# 1_Sheet_1_schdoc.net
KiCad netlist of a schematic drawn in Altium Designer
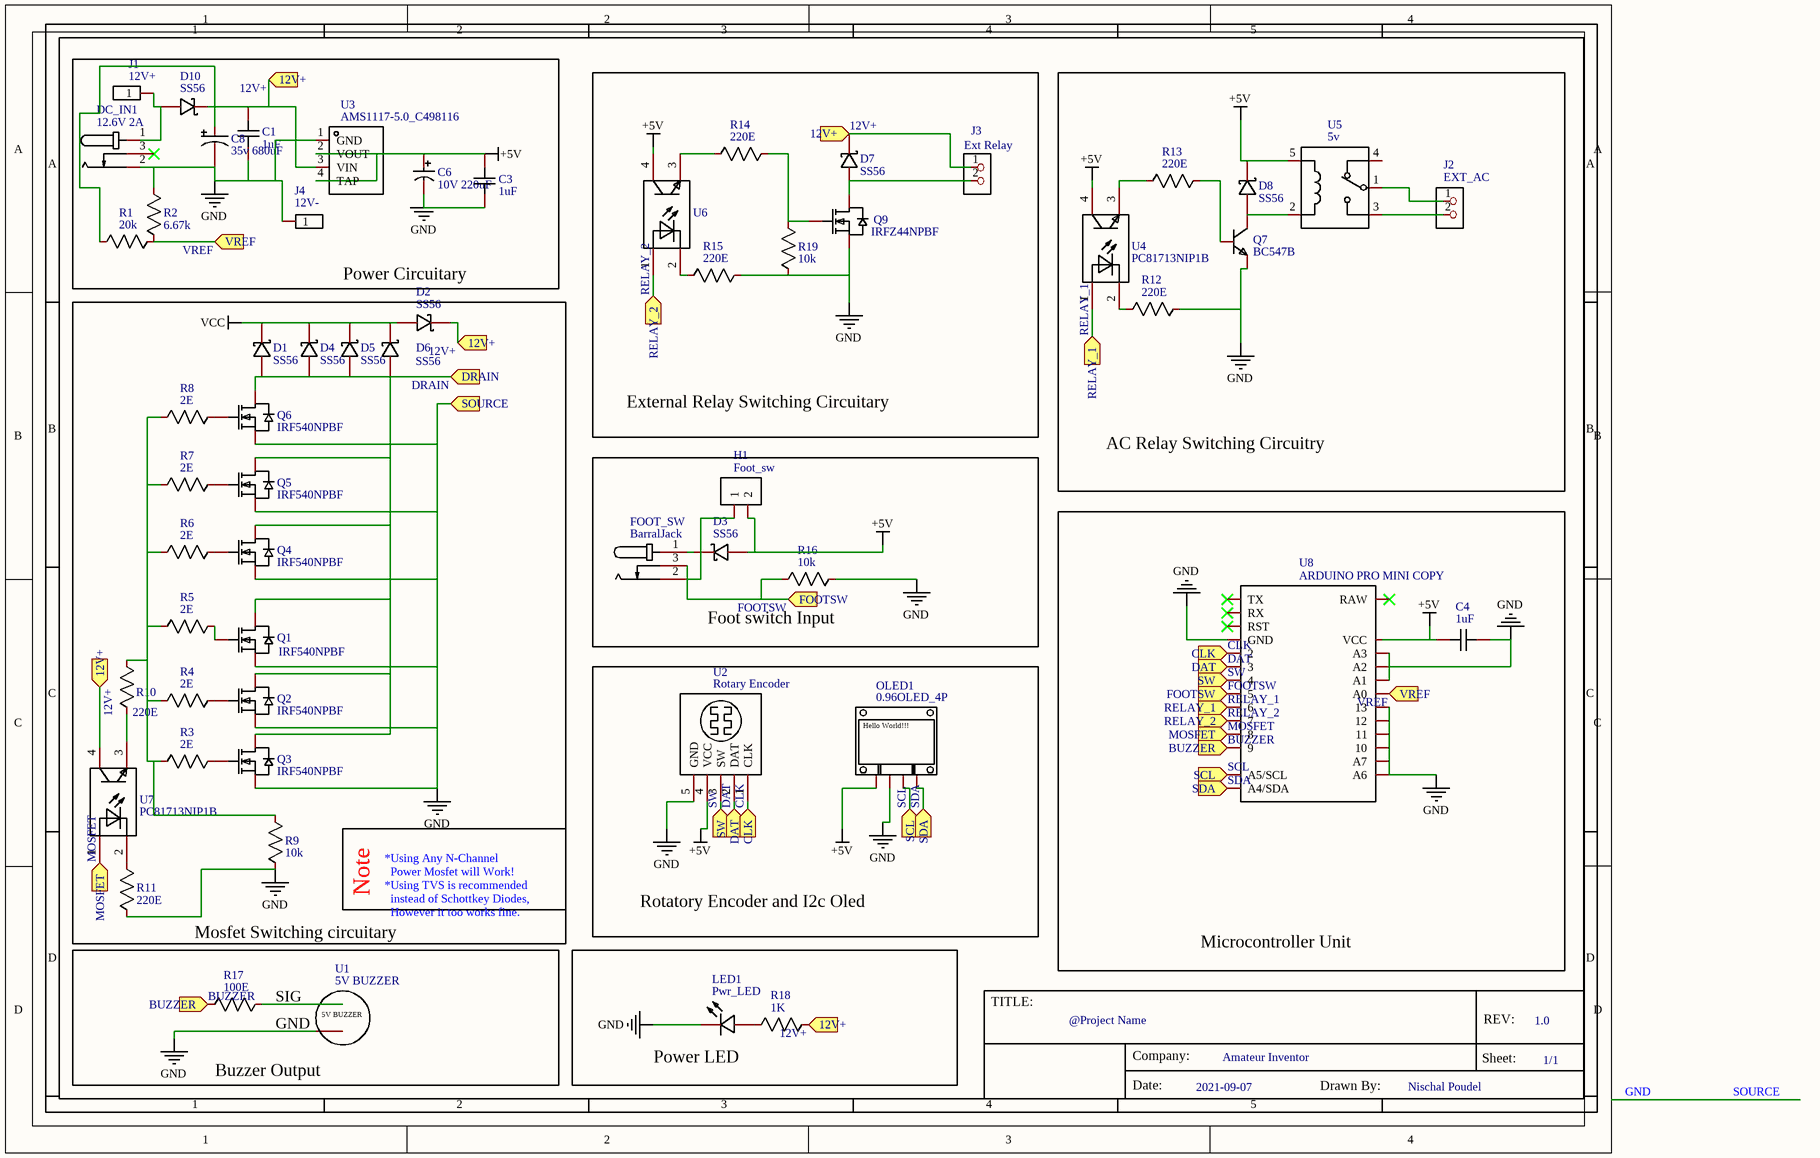
[diagram p0: 1_Sheet_1.schdoc.schdoc]

(export (version "E")
  (design (tool "Eeschema 10.0.6"))
  (components
    (comp (ref "C1")
      (value "1uF")
      (fields
        (field (name "NAME") "1uF")
        (field (name "MANUFACTURER") "FH")
        (field (name "MANUFACTURER PART") "0603B105K160NT")
      )
      (libsource (lib "altium-import") (part "root_1_0603B105K160NT_"))
    )
    (comp (ref "C3")
      (value "1uF")
      (fields
        (field (name "NAME") "1uF")
        (field (name "MANUFACTURER") "FH")
        (field (name "MANUFACTURER PART") "0603B105K160NT")
      )
      (libsource (lib "altium-import") (part "root_1_0603B105K160NT_"))
    )
    (comp (ref "C4")
      (value "1uF")
      (fields
        (field (name "NAME") "1uF")
        (field (name "MANUFACTURER") "FH")
        (field (name "MANUFACTURER PART") "0603B105K160NT")
      )
      (libsource (lib "altium-import") (part "root_2_0603B105K160NT_"))
    )
    (comp (ref "C6")
      (value "10V 220uF")
      (fields
        (field (name "NAME") "10V 220uF")
        (field (name "MANUFACTURER") "ValuePro")
        (field (name "MANUFACTURER PART") "220uF 10V black gold 5*11")
      )
      (libsource (lib "altium-import") (part "root_3_220uF 10V black gold 5*11_"))
    )
    (comp (ref "C8")
      (value "35v 680uF")
      (fields
        (field (name "NAME") "35v 680uF")
        (field (name "MANUFACTURER") "BERYL Electronic Tech")
        (field (name "MANUFACTURER PART") "RC035M681LO10*16TH-2A1E")
      )
      (libsource (lib "altium-import") (part "root_3_RC035M681LO10*16TH-2A1E_"))
    )
    (comp (ref "D1")
      (value "SS56")
      (fields (field (name "NAME") "SS56") (field (name "MANUFACTURER") "High Diode"))
      (libsource (lib "altium-import") (part "root_3_SS56_"))
    )
    (comp (ref "D2")
      (value "SS56")
      (fields (field (name "NAME") "SS56") (field (name "MANUFACTURER") "High Diode"))
      (libsource (lib "altium-import") (part "root_2_SS56_"))
    )
    (comp (ref "D3")
      (value "SS56")
      (fields (field (name "NAME") "SS56") (field (name "MANUFACTURER") "High Diode"))
      (libsource (lib "altium-import") (part "root_0_SS56_"))
    )
    (comp (ref "D4")
      (value "SS56")
      (fields (field (name "NAME") "SS56") (field (name "MANUFACTURER") "High Diode"))
      (libsource (lib "altium-import") (part "root_3_SS56_"))
    )
    (comp (ref "D5")
      (value "SS56")
      (fields (field (name "NAME") "SS56") (field (name "MANUFACTURER") "High Diode"))
      (libsource (lib "altium-import") (part "root_3_SS56_"))
    )
    (comp (ref "D6")
      (value "SS56")
      (fields (field (name "NAME") "SS56") (field (name "MANUFACTURER") "High Diode"))
      (libsource (lib "altium-import") (part "root_3_SS56_"))
    )
    (comp (ref "D7")
      (value "SS56")
      (fields (field (name "NAME") "SS56") (field (name "MANUFACTURER") "High Diode"))
      (libsource (lib "altium-import") (part "root_3_SS56_"))
    )
    (comp (ref "D8")
      (value "SS56")
      (fields (field (name "NAME") "SS56") (field (name "MANUFACTURER") "High Diode"))
      (libsource (lib "altium-import") (part "root_3_SS56_"))
    )
    (comp (ref "D10")
      (value "SS56")
      (fields (field (name "NAME") "SS56") (field (name "MANUFACTURER") "High Diode"))
      (libsource (lib "altium-import") (part "root_2_SS56_"))
    )
    (comp (ref "DC_IN1")
      (value "12.6V 2A")
      (fields
        (field (name "NAME") "12.6V 2A")
        (field (name "MANUFACTURER") "XKB Enterprise")
        (field (name "MANUFACTURER PART") "DC-005B-2.5A-2.0")
      )
      (libsource (lib "altium-import") (part "root_0_DC-005B-2.5A-2.0_"))
    )
    (comp (ref "FOOT_SW")
      (value "BarralJack")
      (fields
        (field (name "NAME") "BarralJack")
        (field (name "MANUFACTURER") "XKB Enterprise")
        (field (name "MANUFACTURER PART") "DC-005B-2.5A-2.0")
      )
      (libsource (lib "altium-import") (part "root_0_DC-005B-2.5A-2.0_"))
    )
    (comp (ref "H1")
      (value "Foot_sw")
      (fields (field (name "NAME") "Foot_sw"))
      (libsource (lib "altium-import") (part "root_1_Foot_sw_"))
    )
    (comp (ref "J1")
      (value "12V+")
      (fields (field (name "NAME") "12V+"))
      (libsource (lib "altium-import") (part "root_2_12V+_"))
    )
    (comp (ref "J2")
      (value "EXT_AC")
      (fields (field (name "NAME") "EXT_AC"))
      (libsource (lib "altium-import") (part "root_0_EXT_AC_"))
    )
    (comp (ref "J3")
      (value "Ext Relay")
      (fields (field (name "NAME") "Ext Relay"))
      (libsource (lib "altium-import") (part "root_0_Ext Relay_"))
    )
    (comp (ref "J4")
      (value "12V-")
      (fields (field (name "NAME") "12V-"))
      (libsource (lib "altium-import") (part "root_0_12V-_"))
    )
    (comp (ref "LED1")
      (value "Pwr_LED")
      (fields
        (field (name "NAME") "Pwr_LED")
        (field (name "MANUFACTURER") "TOGIALED")
        (field (name "MANUFACTURER PART") "TJ-S1608SW6TGLC2G-A5")
      )
      (libsource (lib "altium-import") (part "root_0_TJ-S1608SW6TGLC2G-A5_"))
    )
    (comp (ref "OLED1")
      (value "0.96OLED_4P")
      (fields (field (name "NAME") "0.96OLED_4P"))
      (libsource (lib "altium-import") (part "root_0_0.96OLED_4P_"))
    )
    (comp (ref "Q1")
      (value "IRF540NPBF")
      (fields (field (name "NAME") "IRF540NPBF") (field (name "MANUFACTURER") "Infineon"))
      (libsource (lib "altium-import") (part "root_0_IRF540NPBF_"))
    )
    (comp (ref "Q2")
      (value "IRF540NPBF")
      (fields (field (name "NAME") "IRF540NPBF") (field (name "MANUFACTURER") "Infineon"))
      (libsource (lib "altium-import") (part "root_0_IRF540NPBF_"))
    )
    (comp (ref "Q3")
      (value "IRF540NPBF")
      (fields (field (name "NAME") "IRF540NPBF") (field (name "MANUFACTURER") "Infineon"))
      (libsource (lib "altium-import") (part "root_0_IRF540NPBF_"))
    )
    (comp (ref "Q4")
      (value "IRF540NPBF")
      (fields (field (name "NAME") "IRF540NPBF") (field (name "MANUFACTURER") "Infineon"))
      (libsource (lib "altium-import") (part "root_0_IRF540NPBF_"))
    )
    (comp (ref "Q5")
      (value "IRF540NPBF")
      (fields (field (name "NAME") "IRF540NPBF") (field (name "MANUFACTURER") "Infineon"))
      (libsource (lib "altium-import") (part "root_0_IRF540NPBF_"))
    )
    (comp (ref "Q6")
      (value "IRF540NPBF")
      (fields (field (name "NAME") "IRF540NPBF") (field (name "MANUFACTURER") "Infineon"))
      (libsource (lib "altium-import") (part "root_0_IRF540NPBF_"))
    )
    (comp (ref "Q7")
      (value "BC547B")
      (fields (field (name "NAME") "BC547B") (field (name "MANUFACTURER") "LGE"))
      (libsource (lib "altium-import") (part "root_0_BC547B_"))
    )
    (comp (ref "Q9")
      (value "IRFZ44NPBF")
      (fields (field (name "NAME") "IRFZ44NPBF") (field (name "MANUFACTURER") "Infineon(英飞凌)"))
      (libsource (lib "altium-import") (part "root_0_IRFZ44NPBF_"))
    )
    (comp (ref "R1")
      (value "20k")
      (fields (field (name "NAME") "20k"))
      (libsource (lib "altium-import") (part "root_0_20k_"))
    )
    (comp (ref "R2")
      (value "6.67k")
      (fields (field (name "NAME") "6.67k"))
      (libsource (lib "altium-import") (part "root_3_6.67k_"))
    )
    (comp (ref "R3")
      (value "2E")
      (fields (field (name "NAME") "2E"))
      (libsource (lib "altium-import") (part "root_0_2E_"))
    )
    (comp (ref "R4")
      (value "2E")
      (fields (field (name "NAME") "2E"))
      (libsource (lib "altium-import") (part "root_0_2E_"))
    )
    (comp (ref "R5")
      (value "2E")
      (fields (field (name "NAME") "2E"))
      (libsource (lib "altium-import") (part "root_0_2E_"))
    )
    (comp (ref "R6")
      (value "2E")
      (fields (field (name "NAME") "2E"))
      (libsource (lib "altium-import") (part "root_0_2E_"))
    )
    (comp (ref "R7")
      (value "2E")
      (fields (field (name "NAME") "2E"))
      (libsource (lib "altium-import") (part "root_0_2E_"))
    )
    (comp (ref "R8")
      (value "2E")
      (fields (field (name "NAME") "2E"))
      (libsource (lib "altium-import") (part "root_0_2E_"))
    )
    (comp (ref "R9")
      (value "10k")
      (fields (field (name "NAME") "10k"))
      (libsource (lib "altium-import") (part "root_1_10k_"))
    )
    (comp (ref "R10")
      (value "220E")
      (fields (field (name "NAME") "220E"))
      (libsource (lib "altium-import") (part "root_1_220E_"))
    )
    (comp (ref "R11")
      (value "220E")
      (fields (field (name "NAME") "220E"))
      (libsource (lib "altium-import") (part "root_1_220E_"))
    )
    (comp (ref "R12")
      (value "220E")
      (fields (field (name "NAME") "220E"))
      (libsource (lib "altium-import") (part "root_2_220E_"))
    )
    (comp (ref "R13")
      (value "220E")
      (fields (field (name "NAME") "220E"))
      (libsource (lib "altium-import") (part "root_0_220E_"))
    )
    (comp (ref "R14")
      (value "220E")
      (fields (field (name "NAME") "220E"))
      (libsource (lib "altium-import") (part "root_0_220E_"))
    )
    (comp (ref "R15")
      (value "220E")
      (fields (field (name "NAME") "220E"))
      (libsource (lib "altium-import") (part "root_2_220E_"))
    )
    (comp (ref "R16")
      (value "10k")
      (fields (field (name "NAME") "10k"))
      (libsource (lib "altium-import") (part "root_2_10k_"))
    )
    (comp (ref "R17")
      (value "100E")
      (fields (field (name "NAME") "100E"))
      (libsource (lib "altium-import") (part "root_2_100E_"))
    )
    (comp (ref "R18")
      (value "1K")
      (fields (field (name "NAME") "1K"))
      (libsource (lib "altium-import") (part "root_2_1K_"))
    )
    (comp (ref "R19")
      (value "10k")
      (fields (field (name "NAME") "10k"))
      (libsource (lib "altium-import") (part "root_3_10k_"))
    )
    (comp (ref "U1")
      (value "5V BUZZER")
      (fields (field (name "NAME") "5V BUZZER"))
      (libsource (lib "altium-import") (part "root_0_5V BUZZER_"))
    )
    (comp (ref "U2")
      (value "Rotary Encoder")
      (fields (field (name "NAME") "Rotary Encoder") (field (name "MANUFACTURER PART") "encoder"))
      (libsource (lib "altium-import") (part "root_3_encoder_"))
    )
    (comp (ref "U3")
      (value "AMS1117-5.0_C498116")
      (fields
        (field (name "NAME") "AMS1117-5.0_C498116")
        (field (name "MANUFACTURER") "HGC(Huaguan Semicon)")
        (field (name "MANUFACTURER PART") "AMS1117-5.0")
      )
      (libsource (lib "altium-import") (part "root_0_AMS1117-5.0_"))
    )
    (comp (ref "U4")
      (value "PC81713NIP1B")
      (fields (field (name "NAME") "PC81713NIP1B") (field (name "MANUFACTURER") "Sharp Microelectronics"))
      (libsource (lib "altium-import") (part "root_1_PC81713NIP1B_"))
    )
    (comp (ref "U5")
      (value "5v")
      (fields (field (name "NAME") "5v"))
      (libsource (lib "altium-import") (part "root_0_5v_"))
    )
    (comp (ref "U6")
      (value "PC81713NIP1B")
      (fields (field (name "MANUFACTURER") "Sharp Microelectronics"))
      (libsource (lib "altium-import") (part "root_1_PC81713NIP1B_"))
    )
    (comp (ref "U7")
      (value "PC81713NIP1B")
      (fields (field (name "NAME") "PC81713NIP1B") (field (name "MANUFACTURER") "Sharp Microelectronics"))
      (libsource (lib "altium-import") (part "root_1_PC81713NIP1B_"))
    )
    (comp (ref "U8")
      (value "ARDUINO PRO MINI COPY")
      (description "Arduino Pro Mini footprint")
      (fields (field (name "NAME") "ARDUINO PRO MINI COPY"))
      (libsource (lib "altium-import") (part "root_0_ARDUINO PRO MINI COPY_"))
    )
  )
  (nets
    (net (code "1") (name "+5V") (class "Default")
      (node (ref "C3") (pin "2") (pinfunction "2_2") (pintype "passive"))
      (node (ref "C4") (pin "2") (pinfunction "2_2") (pintype "passive"))
      (node (ref "C6") (pin "1") (pinfunction "1_1") (pintype "passive"))
      (node (ref "D3") (pin "2") (pinfunction "2_2") (pintype "passive"))
      (node (ref "D8") (pin "1") (pinfunction "1_1") (pintype "passive"))
      (node (ref "H1") (pin "2") (pinfunction "2_2") (pintype "passive"))
      (node (ref "OLED1") (pin "1") (pinfunction "1_1") (pintype "passive"))
      (node (ref "U2") (pin "4") (pinfunction "VCC_4") (pintype "passive"))
      (node (ref "U3") (pin "2") (pinfunction "VOUT_2") (pintype "passive"))
      (node (ref "U3") (pin "4") (pinfunction "TAP_4") (pintype "passive"))
      (node (ref "U4") (pin "4") (pinfunction "Collector_4") (pintype "passive"))
      (node (ref "U5") (pin "5") (pinfunction "5_5") (pintype "passive"))
      (node (ref "U6") (pin "4") (pinfunction "Collector_4") (pintype "passive"))
      (node (ref "U8") (pin "VCC") (pinfunction "VCC_VCC") (pintype "passive"))
    )
    (net (code "2") (name "/12V+") (class "Default")
      (node (ref "C1") (pin "2") (pinfunction "2_2") (pintype "passive"))
      (node (ref "C8") (pin "1") (pinfunction "1_1") (pintype "passive"))
      (node (ref "D10") (pin "1") (pinfunction "1_1") (pintype "passive"))
      (node (ref "D2") (pin "1") (pinfunction "1_1") (pintype "passive"))
      (node (ref "D7") (pin "1") (pinfunction "1_1") (pintype "passive"))
      (node (ref "J3") (pin "1") (pinfunction "1_1") (pintype "passive"))
      (node (ref "R1") (pin "1") (pinfunction "1_1") (pintype "passive"))
      (node (ref "R18") (pin "1") (pinfunction "1_1") (pintype "passive"))
      (node (ref "U3") (pin "3") (pinfunction "VIN_3") (pintype "passive"))
      (node (ref "U7") (pin "4") (pinfunction "Collector_4") (pintype "passive"))
    )
    (net (code "3") (name "/BUZZER") (class "Default")
      (node (ref "R17") (pin "2") (pinfunction "2_2") (pintype "passive"))
      (node (ref "U8") (pin "D9") (pinfunction "9_D9") (pintype "passive"))
    )
    (net (code "4") (name "/CLK") (class "Default")
      (node (ref "U2") (pin "1") (pinfunction "CLK_1") (pintype "passive"))
      (node (ref "U8") (pin "D2") (pinfunction "2_D2") (pintype "passive"))
    )
    (net (code "5") (name "/DAT") (class "Default")
      (node (ref "U2") (pin "2") (pinfunction "DAT_2") (pintype "passive"))
      (node (ref "U8") (pin "D3") (pinfunction "3_D3") (pintype "passive"))
    )
    (net (code "6") (name "/DRAIN") (class "Default")
      (node (ref "D1") (pin "2") (pinfunction "2_2") (pintype "passive"))
      (node (ref "D4") (pin "2") (pinfunction "2_2") (pintype "passive"))
      (node (ref "D5") (pin "2") (pinfunction "2_2") (pintype "passive"))
      (node (ref "D6") (pin "2") (pinfunction "2_2") (pintype "passive"))
      (node (ref "Q1") (pin "2") (pinfunction "D_2") (pintype "passive"))
      (node (ref "Q2") (pin "2") (pinfunction "D_2") (pintype "passive"))
      (node (ref "Q3") (pin "2") (pinfunction "D_2") (pintype "passive"))
      (node (ref "Q4") (pin "2") (pinfunction "D_2") (pintype "passive"))
      (node (ref "Q5") (pin "2") (pinfunction "D_2") (pintype "passive"))
      (node (ref "Q6") (pin "2") (pinfunction "D_2") (pintype "passive"))
    )
    (net (code "7") (name "/FOOTSW") (class "Default")
      (node (ref "FOOT_SW") (pin "2") (pinfunction "2_2") (pintype "passive"))
      (node (ref "FOOT_SW") (pin "3") (pinfunction "3_3") (pintype "passive"))
      (node (ref "H1") (pin "1") (pinfunction "1_1") (pintype "passive"))
      (node (ref "R16") (pin "2") (pinfunction "2_2") (pintype "passive"))
      (node (ref "U8") (pin "D5") (pinfunction "5_D5") (pintype "passive"))
    )
    (net (code "8") (name "/MOSFET") (class "Default")
      (node (ref "U7") (pin "1") (pinfunction "Anode_1") (pintype "passive"))
      (node (ref "U8") (pin "D8") (pinfunction "8_D8") (pintype "passive"))
    )
    (net (code "9") (name "/RELAY_1") (class "Default")
      (node (ref "U4") (pin "1") (pinfunction "Anode_1") (pintype "passive"))
      (node (ref "U8") (pin "D6") (pinfunction "6_D6") (pintype "passive"))
    )
    (net (code "10") (name "/RELAY_2") (class "Default")
      (node (ref "U6") (pin "1") (pinfunction "Anode_1") (pintype "passive"))
      (node (ref "U8") (pin "D7") (pinfunction "7_D7") (pintype "passive"))
    )
    (net (code "11") (name "/SCL") (class "Default")
      (node (ref "OLED1") (pin "3") (pinfunction "3_3") (pintype "passive"))
      (node (ref "U8") (pin "A5") (pinfunction "A5/SCL_A5") (pintype "passive"))
    )
    (net (code "12") (name "/SDA") (class "Default")
      (node (ref "OLED1") (pin "4") (pinfunction "4_4") (pintype "passive"))
      (node (ref "U8") (pin "A4") (pinfunction "A4/SDA_A4") (pintype "passive"))
    )
    (net (code "13") (name "/SW") (class "Default")
      (node (ref "U2") (pin "3") (pinfunction "SW_3") (pintype "passive"))
      (node (ref "U8") (pin "D4") (pinfunction "4_D4") (pintype "passive"))
    )
    (net (code "14") (name "/VREF") (class "Default")
      (node (ref "R1") (pin "2") (pinfunction "2_2") (pintype "passive"))
      (node (ref "R2") (pin "2") (pinfunction "2_2") (pintype "passive"))
      (node (ref "U8") (pin "A0") (pinfunction "A0_A0") (pintype "passive"))
    )
    (net (code "15") (name "GND") (class "Default")
      (node (ref "C1") (pin "1") (pinfunction "1_1") (pintype "passive"))
      (node (ref "C3") (pin "1") (pinfunction "1_1") (pintype "passive"))
      (node (ref "C4") (pin "1") (pinfunction "1_1") (pintype "passive"))
      (node (ref "C6") (pin "2") (pinfunction "2_2") (pintype "passive"))
      (node (ref "C8") (pin "2") (pinfunction "2_2") (pintype "passive"))
      (node (ref "DC_IN1") (pin "2") (pinfunction "2_2") (pintype "passive"))
      (node (ref "J4") (pin "1") (pinfunction "1_1") (pintype "passive"))
      (node (ref "LED1") (pin "1") (pinfunction "-_1") (pintype "passive"))
      (node (ref "OLED1") (pin "2") (pinfunction "2_2") (pintype "passive"))
      (node (ref "Q1") (pin "3") (pinfunction "S_3") (pintype "passive"))
      (node (ref "Q2") (pin "3") (pinfunction "S_3") (pintype "passive"))
      (node (ref "Q3") (pin "3") (pinfunction "S_3") (pintype "passive"))
      (node (ref "Q4") (pin "3") (pinfunction "S_3") (pintype "passive"))
      (node (ref "Q5") (pin "3") (pinfunction "S_3") (pintype "passive"))
      (node (ref "Q6") (pin "3") (pinfunction "S_3") (pintype "passive"))
      (node (ref "Q7") (pin "3") (pinfunction "E_3") (pintype "passive"))
      (node (ref "Q9") (pin "3") (pinfunction "S_3") (pintype "passive"))
      (node (ref "R11") (pin "1") (pinfunction "1_1") (pintype "passive"))
      (node (ref "R12") (pin "1") (pinfunction "1_1") (pintype "passive"))
      (node (ref "R15") (pin "1") (pinfunction "1_1") (pintype "passive"))
      (node (ref "R16") (pin "1") (pinfunction "1_1") (pintype "passive"))
      (node (ref "R19") (pin "2") (pinfunction "2_2") (pintype "passive"))
      (node (ref "R2") (pin "1") (pinfunction "1_1") (pintype "passive"))
      (node (ref "R9") (pin "1") (pinfunction "1_1") (pintype "passive"))
      (node (ref "U2") (pin "5") (pinfunction "GND_5") (pintype "passive"))
      (node (ref "U3") (pin "1") (pinfunction "GND_1") (pintype "passive"))
      (node (ref "U8") (pin "A1") (pinfunction "A1_A1") (pintype "passive"))
      (node (ref "U8") (pin "A2") (pinfunction "A2_A2") (pintype "passive"))
      (node (ref "U8") (pin "A3") (pinfunction "A3_A3") (pintype "passive"))
      (node (ref "U8") (pin "A6") (pinfunction "A6_A6") (pintype "passive"))
      (node (ref "U8") (pin "A7") (pinfunction "A7_A7") (pintype "passive"))
      (node (ref "U8") (pin "D10") (pinfunction "10_D10") (pintype "passive"))
      (node (ref "U8") (pin "D11") (pinfunction "11_D11") (pintype "passive"))
      (node (ref "U8") (pin "D12") (pinfunction "12_D12") (pintype "passive"))
      (node (ref "U8") (pin "D13") (pinfunction "13_D13") (pintype "passive"))
      (node (ref "U8") (pin "GND") (pinfunction "GND_GND") (pintype "passive"))
    )
    (net (code "16") (name "Net-(D3-Pad1)") (class "Default")
      (node (ref "D3") (pin "1") (pinfunction "1_1") (pintype "passive"))
      (node (ref "FOOT_SW") (pin "1") (pinfunction "1_1") (pintype "passive"))
    )
    (net (code "17") (name "Net-(D10-Pad2)") (class "Default")
      (node (ref "D10") (pin "2") (pinfunction "2_2") (pintype "passive"))
      (node (ref "DC_IN1") (pin "1") (pinfunction "1_1") (pintype "passive"))
      (node (ref "J1") (pin "1") (pinfunction "1_1") (pintype "passive"))
    )
    (net (code "18") (name "Net-(J2-Pad1)") (class "Default")
      (node (ref "J2") (pin "1") (pinfunction "1_1") (pintype "passive"))
      (node (ref "U5") (pin "1") (pinfunction "1_1") (pintype "passive"))
    )
    (net (code "19") (name "Net-(J2-Pad2)") (class "Default")
      (node (ref "J2") (pin "2") (pinfunction "2_2") (pintype "passive"))
      (node (ref "U5") (pin "3") (pinfunction "3_3") (pintype "passive"))
    )
    (net (code "20") (name "Net-(LED1-+)") (class "Default")
      (node (ref "LED1") (pin "2") (pinfunction "+_2") (pintype "passive"))
      (node (ref "R18") (pin "2") (pinfunction "2_2") (pintype "passive"))
    )
    (net (code "21") (name "Net-(Q1-G)") (class "Default")
      (node (ref "Q1") (pin "1") (pinfunction "G_1") (pintype "passive"))
      (node (ref "R5") (pin "2") (pinfunction "2_2") (pintype "passive"))
    )
    (net (code "22") (name "Net-(Q2-G)") (class "Default")
      (node (ref "Q2") (pin "1") (pinfunction "G_1") (pintype "passive"))
      (node (ref "R4") (pin "2") (pinfunction "2_2") (pintype "passive"))
    )
    (net (code "23") (name "Net-(Q3-G)") (class "Default")
      (node (ref "Q3") (pin "1") (pinfunction "G_1") (pintype "passive"))
      (node (ref "R3") (pin "2") (pinfunction "2_2") (pintype "passive"))
    )
    (net (code "24") (name "Net-(Q4-G)") (class "Default")
      (node (ref "Q4") (pin "1") (pinfunction "G_1") (pintype "passive"))
      (node (ref "R6") (pin "2") (pinfunction "2_2") (pintype "passive"))
    )
    (net (code "25") (name "Net-(Q5-G)") (class "Default")
      (node (ref "Q5") (pin "1") (pinfunction "G_1") (pintype "passive"))
      (node (ref "R7") (pin "2") (pinfunction "2_2") (pintype "passive"))
    )
    (net (code "26") (name "Net-(Q6-G)") (class "Default")
      (node (ref "Q6") (pin "1") (pinfunction "G_1") (pintype "passive"))
      (node (ref "R8") (pin "2") (pinfunction "2_2") (pintype "passive"))
    )
    (net (code "27") (name "Net-(Q7-B)") (class "Default")
      (node (ref "Q7") (pin "2") (pinfunction "B_2") (pintype "passive"))
      (node (ref "R13") (pin "2") (pinfunction "2_2") (pintype "passive"))
    )
    (net (code "28") (name "Net-(Q7-C)") (class "Default")
      (node (ref "D8") (pin "2") (pinfunction "2_2") (pintype "passive"))
      (node (ref "Q7") (pin "1") (pinfunction "C_1") (pintype "passive"))
      (node (ref "U5") (pin "2") (pinfunction "2_2") (pintype "passive"))
    )
    (net (code "29") (name "Net-(Q9-D)") (class "Default")
      (node (ref "D7") (pin "2") (pinfunction "2_2") (pintype "passive"))
      (node (ref "J3") (pin "2") (pinfunction "2_2") (pintype "passive"))
      (node (ref "Q9") (pin "2") (pinfunction "D_2") (pintype "passive"))
    )
    (net (code "30") (name "Net-(Q9-G)") (class "Default")
      (node (ref "Q9") (pin "1") (pinfunction "G_1") (pintype "passive"))
      (node (ref "R14") (pin "2") (pinfunction "2_2") (pintype "passive"))
      (node (ref "R19") (pin "1") (pinfunction "1_1") (pintype "passive"))
    )
    (net (code "31") (name "Net-(R10-Pad2)") (class "Default")
      (node (ref "R10") (pin "2") (pinfunction "2_2") (pintype "passive"))
      (node (ref "R3") (pin "1") (pinfunction "1_1") (pintype "passive"))
      (node (ref "R4") (pin "1") (pinfunction "1_1") (pintype "passive"))
      (node (ref "R5") (pin "1") (pinfunction "1_1") (pintype "passive"))
      (node (ref "R6") (pin "1") (pinfunction "1_1") (pintype "passive"))
      (node (ref "R7") (pin "1") (pinfunction "1_1") (pintype "passive"))
      (node (ref "R8") (pin "1") (pinfunction "1_1") (pintype "passive"))
      (node (ref "R9") (pin "2") (pinfunction "2_2") (pintype "passive"))
    )
    (net (code "32") (name "Net-(R17-Pad1)") (class "Default")
      (node (ref "R17") (pin "1") (pinfunction "1_1") (pintype "passive"))
      (node (ref "U1") (pin "1") (pinfunction "1_1") (pintype "passive"))
    )
    (net (code "33") (name "Net-(U4-Cathode)") (class "Default")
      (node (ref "R12") (pin "2") (pinfunction "2_2") (pintype "passive"))
      (node (ref "U4") (pin "2") (pinfunction "Cathode_2") (pintype "passive"))
    )
    (net (code "34") (name "Net-(U4-Emitter)") (class "Default")
      (node (ref "R13") (pin "1") (pinfunction "1_1") (pintype "passive"))
      (node (ref "U4") (pin "3") (pinfunction "Emitter_3") (pintype "passive"))
    )
    (net (code "35") (name "Net-(U6-Cathode)") (class "Default")
      (node (ref "R15") (pin "2") (pinfunction "2_2") (pintype "passive"))
      (node (ref "U6") (pin "2") (pinfunction "Cathode_2") (pintype "passive"))
    )
    (net (code "36") (name "Net-(U6-Emitter)") (class "Default")
      (node (ref "R14") (pin "1") (pinfunction "1_1") (pintype "passive"))
      (node (ref "U6") (pin "3") (pinfunction "Emitter_3") (pintype "passive"))
    )
    (net (code "37") (name "Net-(U7-Cathode)") (class "Default")
      (node (ref "R11") (pin "2") (pinfunction "2_2") (pintype "passive"))
      (node (ref "U7") (pin "2") (pinfunction "Cathode_2") (pintype "passive"))
    )
    (net (code "38") (name "Net-(U7-Emitter)") (class "Default")
      (node (ref "R10") (pin "1") (pinfunction "1_1") (pintype "passive"))
      (node (ref "U7") (pin "3") (pinfunction "Emitter_3") (pintype "passive"))
    )
    (net (code "39") (name "VCC") (class "Default")
      (node (ref "D1") (pin "1") (pinfunction "1_1") (pintype "passive"))
      (node (ref "D2") (pin "2") (pinfunction "2_2") (pintype "passive"))
      (node (ref "D4") (pin "1") (pinfunction "1_1") (pintype "passive"))
      (node (ref "D5") (pin "1") (pinfunction "1_1") (pintype "passive"))
      (node (ref "D6") (pin "1") (pinfunction "1_1") (pintype "passive"))
    )
    (net (code "40") (name "unconnected-(DC_IN1-Pad3)") (class "Default")
      (node (ref "DC_IN1") (pin "3") (pinfunction "3_3") (pintype "passive+no_connect"))
    )
    (net (code "41") (name "unconnected-(U1-Pad2)") (class "Default")
      (node (ref "U1") (pin "2") (pinfunction "2_2") (pintype "passive"))
    )
    (net (code "42") (name "unconnected-(U5-Pad4)") (class "Default")
      (node (ref "U5") (pin "4") (pinfunction "4_4") (pintype "passive"))
    )
    (net (code "43") (name "unconnected-(U8-PadRAW)") (class "Default")
      (node (ref "U8") (pin "RAW") (pinfunction "RAW_RAW") (pintype "passive+no_connect"))
    )
    (net (code "44") (name "unconnected-(U8-PadRST)") (class "Default")
      (node (ref "U8") (pin "RST") (pinfunction "RST_RST") (pintype "passive+no_connect"))
    )
    (net (code "45") (name "unconnected-(U8-PadRX)") (class "Default")
      (node (ref "U8") (pin "RX") (pinfunction "RX_RX") (pintype "passive+no_connect"))
    )
    (net (code "46") (name "unconnected-(U8-PadTX)") (class "Default")
      (node (ref "U8") (pin "TX") (pinfunction "TX_TX") (pintype "passive+no_connect"))
    )
  )
)
